# Super-Regenerative-Receiver-2Transistor-.net
KiCad netlist of a schematic drawn in EAGLE
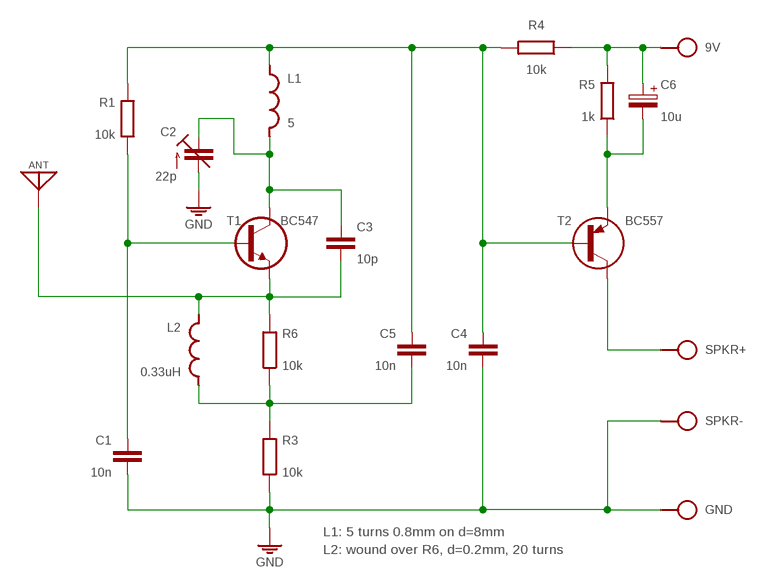
[diagram p0: schematic, sheet 1]

(export (version "E")
  (design (tool "Eeschema 10.0.6"))
  (components
    (comp (ref "9V")
      (value "SPAD")
      (footprint "eagle-import:SPAD")
      (libsource (lib "eagle-import") (part "SPAD"))
    )
    (comp (ref "ANT")
      (value "ANT")
      (footprint "eagle-import:SPAD")
      (libsource (lib "eagle-import") (part "ANT"))
    )
    (comp (ref "C1")
      (value "10n")
      (footprint "eagle-import:C050-020X036")
      (libsource (lib "eagle-import") (part "C050-020X036"))
    )
    (comp (ref "C2")
      (value "22p")
      (footprint "eagle-import:TRIM-2222-808")
      (libsource (lib "eagle-import") (part "C-TR-PH201272222-808-2PINB"))
    )
    (comp (ref "C3")
      (value "10p")
      (footprint "eagle-import:C050-020X036")
      (libsource (lib "eagle-import") (part "C050-020X036"))
    )
    (comp (ref "C4")
      (value "10n")
      (footprint "eagle-import:C050-020X036_V")
      (libsource (lib "eagle-import") (part "C050-020X036/V"))
    )
    (comp (ref "C5")
      (value "10n")
      (footprint "eagle-import:C050-020X036_V")
      (libsource (lib "eagle-import") (part "C050-020X036/V"))
    )
    (comp (ref "C6")
      (value "10u")
      (footprint "eagle-import:E2,5-3")
      (libsource (lib "eagle-import") (part "CPOLE2,5-3"))
    )
    (comp (ref "GND")
      (value "SPAD")
      (footprint "eagle-import:SPAD")
      (libsource (lib "eagle-import") (part "SPAD"))
    )
    (comp (ref "L1")
      (value "5")
      (footprint "eagle-import:L-04_7V-X")
      (libsource (lib "eagle-import") (part "L-SHORTL-04/7V-X"))
    )
    (comp (ref "L2")
      (value "0.33uH")
      (footprint "eagle-import:L-04_7V-X")
      (libsource (lib "eagle-import") (part "L-SHORTL-04/7V-X"))
    )
    (comp (ref "R1")
      (value "10k")
      (footprint "eagle-import:0202_7")
      (libsource (lib "eagle-import") (part "R0202/7"))
    )
    (comp (ref "R3")
      (value "10k")
      (footprint "eagle-import:0202V")
      (libsource (lib "eagle-import") (part "R0202V"))
    )
    (comp (ref "R4")
      (value "10k")
      (footprint "eagle-import:0202_7")
      (libsource (lib "eagle-import") (part "R0202/7"))
    )
    (comp (ref "R5")
      (value "1k")
      (footprint "eagle-import:0202_7-V")
      (libsource (lib "eagle-import") (part "R0202/7-V"))
    )
    (comp (ref "R6")
      (value "10k")
      (footprint "eagle-import:0202_7-V")
      (libsource (lib "eagle-import") (part "R0202/7-V"))
    )
    (comp (ref "SPKR+")
      (value "SPAD")
      (footprint "eagle-import:SPAD")
      (libsource (lib "eagle-import") (part "SPAD"))
    )
    (comp (ref "SPKR-")
      (value "SPAD")
      (footprint "eagle-import:SPAD")
      (libsource (lib "eagle-import") (part "SPAD"))
    )
    (comp (ref "T1")
      (value "BC547")
      (footprint "eagle-import:TO92-CBE")
      (libsource (lib "eagle-import") (part "BC547CBE"))
    )
    (comp (ref "T2")
      (value "BC557")
      (footprint "eagle-import:TO92-CBE-A")
      (libsource (lib "eagle-import") (part "BC557CBE-A"))
    )
  )
  (nets
    (net (code "1") (name "GND") (class "Default")
      (node (ref "C1") (pin "2") (pinfunction "2_2") (pintype "passive"))
      (node (ref "C2") (pin "2") (pinfunction "A_2") (pintype "passive"))
      (node (ref "C4") (pin "2") (pinfunction "2_2") (pintype "passive"))
      (node (ref "GND") (pin "1") (pinfunction "P$1_1") (pintype "bidirectional"))
      (node (ref "R3") (pin "1") (pinfunction "1_1") (pintype "passive"))
      (node (ref "SPKR-") (pin "1") (pinfunction "P$1_1") (pintype "bidirectional"))
    )
    (net (code "2") (name "Net-(9V-P$1)") (class "Default")
      (node (ref "9V") (pin "1") (pinfunction "P$1_1") (pintype "bidirectional"))
      (node (ref "C6") (pin "+") (pinfunction "+_+") (pintype "passive"))
      (node (ref "R4") (pin "1") (pinfunction "1_1") (pintype "passive"))
      (node (ref "R5") (pin "2") (pinfunction "2_2") (pintype "passive"))
    )
    (net (code "3") (name "Net-(ANT-Pad1)") (class "Default")
      (node (ref "ANT") (pin "1") (pinfunction "1_1") (pintype "output"))
      (node (ref "C3") (pin "2") (pinfunction "2_2") (pintype "passive"))
      (node (ref "L2") (pin "2") (pinfunction "2_2") (pintype "passive"))
      (node (ref "R6") (pin "2") (pinfunction "2_2") (pintype "passive"))
      (node (ref "T1") (pin "E") (pinfunction "E_E") (pintype "passive"))
    )
    (net (code "4") (name "Net-(C1-Pad1)") (class "Default")
      (node (ref "C1") (pin "1") (pinfunction "1_1") (pintype "passive"))
      (node (ref "R1") (pin "1") (pinfunction "1_1") (pintype "passive"))
      (node (ref "T1") (pin "B") (pinfunction "B_B") (pintype "passive"))
    )
    (net (code "5") (name "Net-(C2-E)") (class "Default")
      (node (ref "C2") (pin "3") (pinfunction "E_3") (pintype "passive"))
      (node (ref "C3") (pin "1") (pinfunction "1_1") (pintype "passive"))
      (node (ref "L1") (pin "1") (pinfunction "1_1") (pintype "passive"))
      (node (ref "T1") (pin "C") (pinfunction "C_C") (pintype "passive"))
    )
    (net (code "6") (name "Net-(C4-Pad1)") (class "Default")
      (node (ref "C4") (pin "1") (pinfunction "1_1") (pintype "passive"))
      (node (ref "C5") (pin "1") (pinfunction "1_1") (pintype "passive"))
      (node (ref "L1") (pin "2") (pinfunction "2_2") (pintype "passive"))
      (node (ref "R1") (pin "2") (pinfunction "2_2") (pintype "passive"))
      (node (ref "R4") (pin "2") (pinfunction "2_2") (pintype "passive"))
      (node (ref "T2") (pin "B") (pinfunction "B_B") (pintype "passive"))
    )
    (net (code "7") (name "Net-(C5-Pad2)") (class "Default")
      (node (ref "C5") (pin "2") (pinfunction "2_2") (pintype "passive"))
      (node (ref "L2") (pin "1") (pinfunction "1_1") (pintype "passive"))
      (node (ref "R3") (pin "2") (pinfunction "2_2") (pintype "passive"))
      (node (ref "R6") (pin "1") (pinfunction "1_1") (pintype "passive"))
    )
    (net (code "8") (name "Net-(C6-Pad-)") (class "Default")
      (node (ref "C6") (pin "-") (pinfunction "-_-") (pintype "passive"))
      (node (ref "R5") (pin "1") (pinfunction "1_1") (pintype "passive"))
      (node (ref "T2") (pin "E") (pinfunction "E_E") (pintype "passive"))
    )
    (net (code "9") (name "Net-(SPKR+-P$1)") (class "Default")
      (node (ref "SPKR+") (pin "1") (pinfunction "P$1_1") (pintype "bidirectional"))
      (node (ref "T2") (pin "C") (pinfunction "C_C") (pintype "passive"))
    )
  )
)
